# EMMA_bus.net
KiCad netlist of a schematic drawn in EAGLE
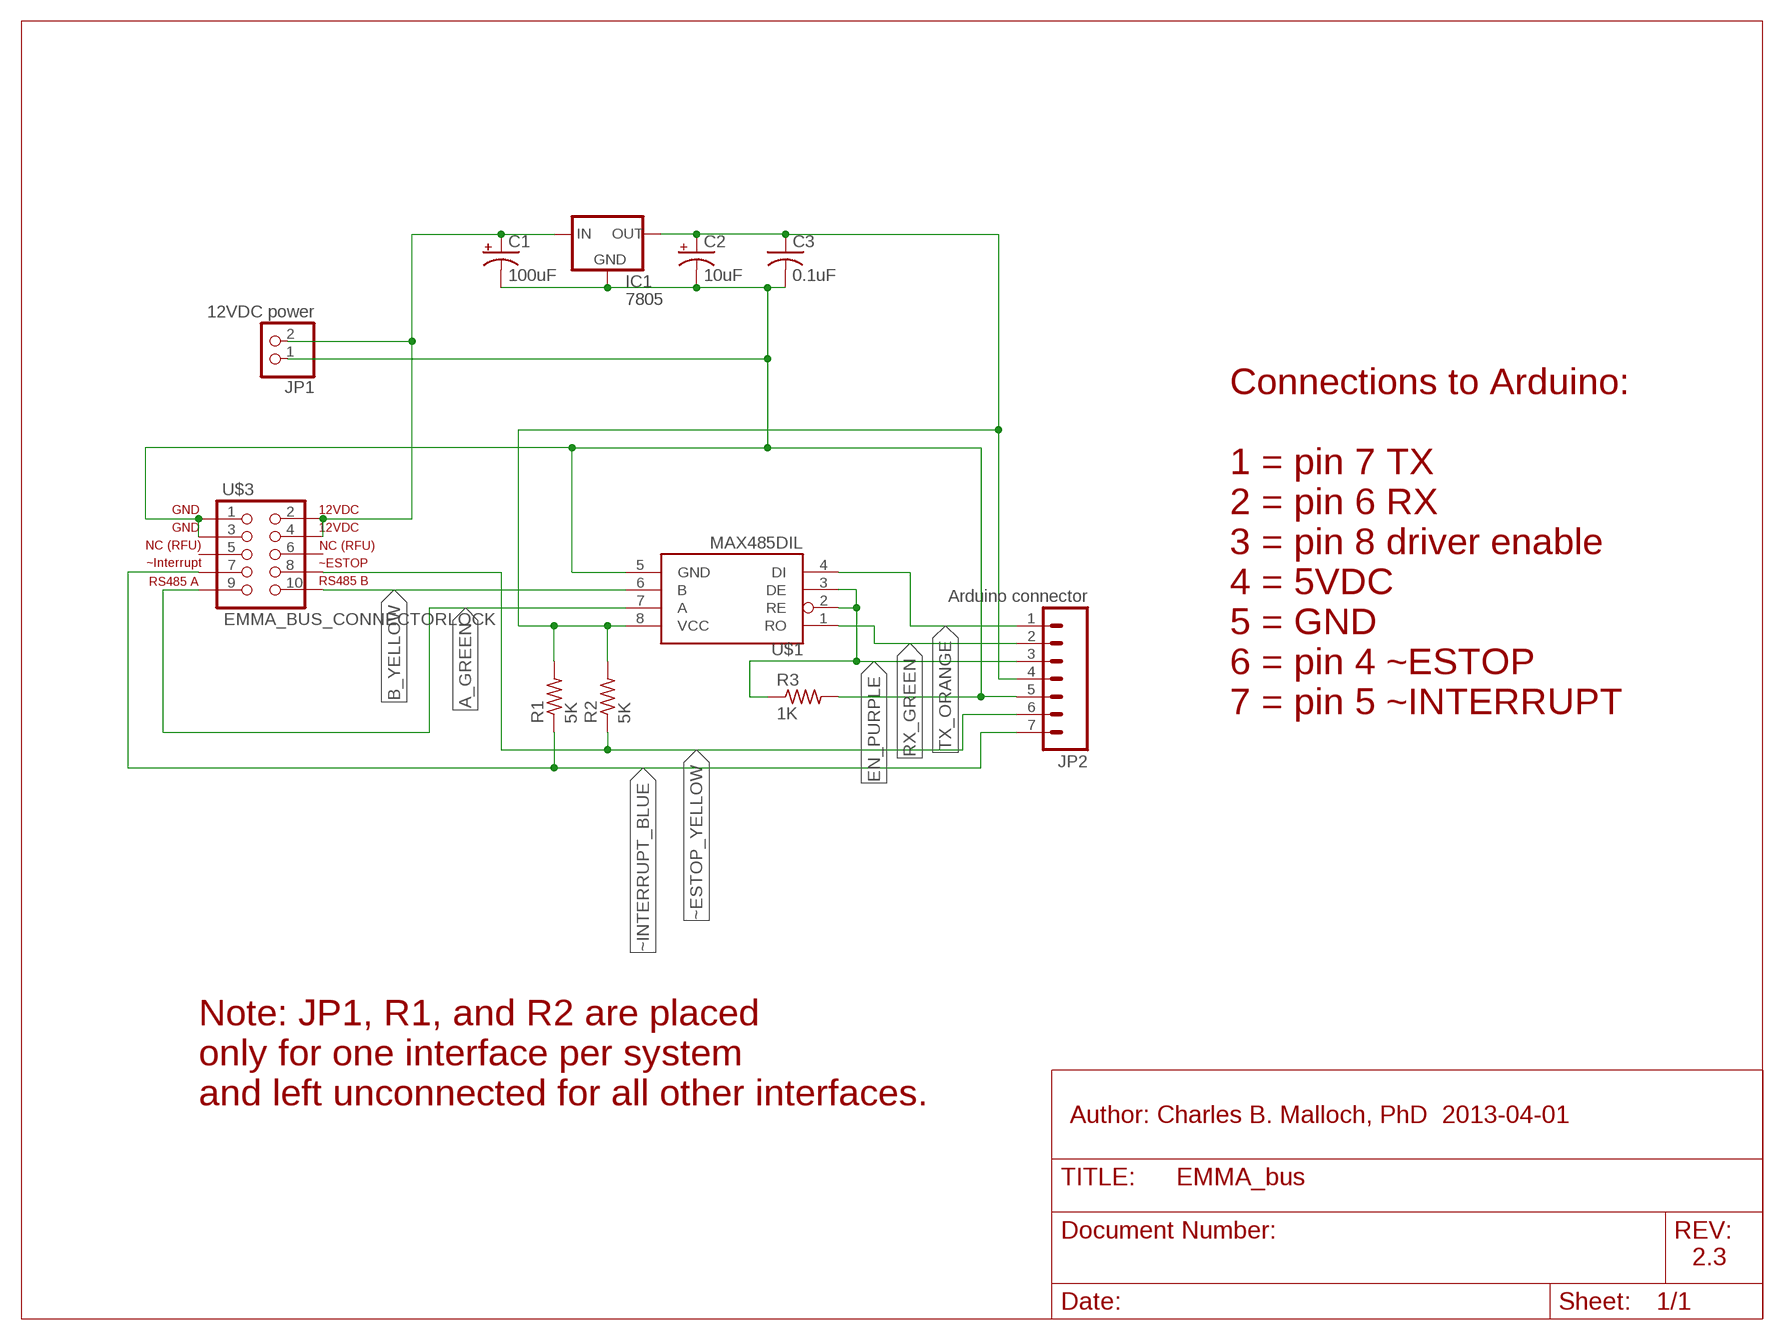
[diagram p0: schematic, sheet 1]

(export (version "E")
  (design (tool "Eeschema 10.0.6"))
  (components
    (comp (ref "C1")
      (value "100uF")
      (footprint "eagle-import:TT2D7")
      (libsource (lib "eagle-import") (part "CPOL-USTT2D7"))
    )
    (comp (ref "C2")
      (value "10uF")
      (footprint "eagle-import:E1,8-4")
      (libsource (lib "eagle-import") (part "CPOL-USE1.8-4"))
    )
    (comp (ref "C3")
      (value "0.1uF")
      (footprint "eagle-import:C025-025X050")
      (libsource (lib "eagle-import") (part "C-US025-025X050"))
    )
    (comp (ref "IC1")
      (value "7805")
      (footprint "eagle-import:TO-220-ALT")
      (libsource (lib "eagle-import") (part "V_REG_78XX-TO-220"))
    )
    (comp (ref "JP1")
      (value "12VDC power")
      (footprint "eagle-import:1X02")
      (libsource (lib "eagle-import") (part "PINHD-1X2"))
    )
    (comp (ref "JP2")
      (value "Arduino connector")
      (footprint "eagle-import:1X07_LOCK_LONGPADS")
      (libsource (lib "eagle-import") (part "M07LOCK_LONGPADS"))
    )
    (comp (ref "R1")
      (value "5K")
      (footprint "eagle-import:0309_12")
      (libsource (lib "eagle-import") (part "resistor_R-US_0309/12"))
    )
    (comp (ref "R2")
      (value "5K")
      (footprint "eagle-import:0309_12")
      (libsource (lib "eagle-import") (part "resistor_R-US_0309/12"))
    )
    (comp (ref "R3")
      (value "1K")
      (footprint "eagle-import:0207_5V")
      (libsource (lib "eagle-import") (part "R-US_0207/5V"))
    )
    (comp (ref "U$1")
      (value "MAX485DIL")
      (footprint "eagle-import:DIL08")
      (libsource (lib "eagle-import") (part "MAX485DIL"))
    )
    (comp (ref "U$3")
      (value "EMMA_BUS_CONNECTORLOCK")
      (footprint "eagle-import:2X5-SHROUDED_LOCK")
      (libsource (lib "eagle-import") (part "EMMA_BUS_CONNECTORLOCK"))
    )
  )
  (nets
    (net (code "1") (name "/~{ESTOP_YELLOW}") (class "Default")
      (node (ref "JP2") (pin "6") (pinfunction "6_6") (pintype "passive"))
      (node (ref "R2") (pin "1") (pinfunction "1_1") (pintype "passive"))
      (node (ref "U$3") (pin "8") (pinfunction "8_8") (pintype "passive"))
    )
    (net (code "2") (name "/~{INTERRUPT_BLUE}") (class "Default")
      (node (ref "JP2") (pin "7") (pinfunction "7_7") (pintype "passive"))
      (node (ref "R1") (pin "1") (pinfunction "1_1") (pintype "passive"))
      (node (ref "U$3") (pin "7") (pinfunction "7_7") (pintype "passive"))
    )
    (net (code "3") (name "A_GREEN") (class "Default")
      (node (ref "U$1") (pin "7") (pinfunction "A_7") (pintype "bidirectional"))
      (node (ref "U$3") (pin "9") (pinfunction "9_9") (pintype "passive"))
    )
    (net (code "4") (name "B_YELLOW") (class "Default")
      (node (ref "U$1") (pin "6") (pinfunction "B_6") (pintype "bidirectional"))
      (node (ref "U$3") (pin "10") (pinfunction "10_10") (pintype "passive"))
    )
    (net (code "5") (name "EN_PURPLE") (class "Default")
      (node (ref "JP2") (pin "3") (pinfunction "3_3") (pintype "passive"))
      (node (ref "R3") (pin "1") (pinfunction "1_1") (pintype "passive"))
      (node (ref "U$1") (pin "2") (pinfunction "RE_2") (pintype "bidirectional"))
      (node (ref "U$1") (pin "3") (pinfunction "DE_3") (pintype "bidirectional"))
    )
    (net (code "6") (name "Net-(C1-Pad+)") (class "Default")
      (node (ref "C1") (pin "+") (pinfunction "+_+") (pintype "passive"))
      (node (ref "IC1") (pin "IN") (pinfunction "IN_IN") (pintype "input"))
      (node (ref "JP1") (pin "2") (pinfunction "2_2") (pintype "passive"))
      (node (ref "U$3") (pin "2") (pinfunction "2_2") (pintype "passive"))
      (node (ref "U$3") (pin "4") (pinfunction "4_4") (pintype "passive"))
    )
    (net (code "7") (name "Net-(U$1-GND)") (class "Default")
      (node (ref "C1") (pin "-") (pinfunction "-_-") (pintype "passive"))
      (node (ref "C2") (pin "-") (pinfunction "-_-") (pintype "passive"))
      (node (ref "C3") (pin "2") (pinfunction "2_2") (pintype "passive"))
      (node (ref "IC1") (pin "GND") (pinfunction "GND_GND") (pintype "input"))
      (node (ref "JP1") (pin "1") (pinfunction "1_1") (pintype "passive"))
      (node (ref "JP2") (pin "5") (pinfunction "5_5") (pintype "passive"))
      (node (ref "R3") (pin "2") (pinfunction "2_2") (pintype "passive"))
      (node (ref "U$1") (pin "5") (pinfunction "GND_5") (pintype "bidirectional"))
      (node (ref "U$3") (pin "1") (pinfunction "1_1") (pintype "passive"))
      (node (ref "U$3") (pin "3") (pinfunction "3_3") (pintype "passive"))
    )
    (net (code "8") (name "Net-(U$1-VCC)") (class "Default")
      (node (ref "C2") (pin "+") (pinfunction "+_+") (pintype "passive"))
      (node (ref "C3") (pin "1") (pinfunction "1_1") (pintype "passive"))
      (node (ref "IC1") (pin "OUT") (pinfunction "OUT_OUT") (pintype "output"))
      (node (ref "JP2") (pin "4") (pinfunction "4_4") (pintype "passive"))
      (node (ref "R1") (pin "2") (pinfunction "2_2") (pintype "passive"))
      (node (ref "R2") (pin "2") (pinfunction "2_2") (pintype "passive"))
      (node (ref "U$1") (pin "8") (pinfunction "VCC_8") (pintype "bidirectional"))
    )
    (net (code "9") (name "RX_GREEN") (class "Default")
      (node (ref "JP2") (pin "2") (pinfunction "2_2") (pintype "passive"))
      (node (ref "U$1") (pin "1") (pinfunction "RO_1") (pintype "bidirectional"))
    )
    (net (code "10") (name "TX_ORANGE") (class "Default")
      (node (ref "JP2") (pin "1") (pinfunction "1_1") (pintype "passive"))
      (node (ref "U$1") (pin "4") (pinfunction "DI_4") (pintype "bidirectional"))
    )
    (net (code "11") (name "unconnected-(U$3-Pad5)") (class "Default")
      (node (ref "U$3") (pin "5") (pinfunction "5_5") (pintype "passive"))
    )
    (net (code "12") (name "unconnected-(U$3-Pad6)") (class "Default")
      (node (ref "U$3") (pin "6") (pinfunction "6_6") (pintype "passive"))
    )
  )
)
